# Debug_LEDs.net
KiCad netlist of a schematic drawn in Altium Designer
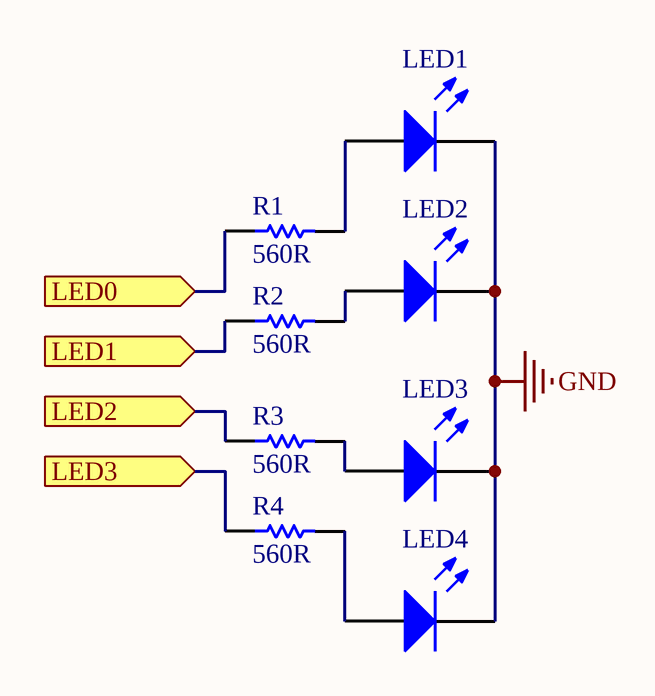
[diagram p0: Debug LEDs.SchDoc]

(export (version "E")
  (design (tool "Eeschema 10.0.6"))
  (components
    (comp (ref "LED1")
      (value "150080RS75000")
      (footprint "0805_A")
      (description "SMD mono-color Chip LED, WL-SMCW, Red")
      (fields (field (name "MANUFACTURER") "Wuerth Elektronik"))
      (libsource (lib "Altium Content Vault") (part "WE-LED_K1A2-2"))
    )
    (comp (ref "LED2")
      (value "150080GS75000")
      (footprint "0805_A")
      (description "SMD mono-color Chip LED, WL-SMCW, Green")
      (fields (field (name "MANUFACTURER") "Wuerth Elektronik"))
      (libsource (lib "Altium Content Vault") (part "WE-LED_K1A2-2"))
    )
    (comp (ref "LED3")
      (value "150080BS75000")
      (footprint "0805_A")
      (description "SMD mono-color Chip LED, WL-SMCW, Blue")
      (fields (field (name "MANUFACTURER") "Wuerth Elektronik"))
      (libsource (lib "Altium Content Vault") (part "WE-LED_K1A2-2"))
    )
    (comp (ref "LED4")
      (value "150080YS75000")
      (footprint "0805_A")
      (description "SMD mono-color Chip LED, WL-SMCW, Yellow")
      (fields (field (name "MANUFACTURER") "Wuerth Elektronik"))
      (libsource (lib "Altium Content Vault") (part "WE-LED_K1A2-2"))
    )
    (comp (ref "R1")
      (value "560R")
      (footprint "RESC0805(2012)_M")
      (description "560R 0.125W 1% 0805 (2012 Metric)  SMD")
      (fields (field (name "TOLERANCE") "1 %") (field (name "POWER") "0.125 W"))
      (libsource (lib "Altium Content Vault") (part "RES"))
    )
    (comp (ref "R2")
      (value "560R")
      (footprint "RESC0805(2012)_M")
      (description "560R 0.125W 1% 0805 (2012 Metric)  SMD")
      (fields (field (name "TOLERANCE") "1 %") (field (name "POWER") "0.125 W"))
      (libsource (lib "Altium Content Vault") (part "RES"))
    )
    (comp (ref "R3")
      (value "560R")
      (footprint "RESC0805(2012)_M")
      (description "560R 0.125W 1% 0805 (2012 Metric)  SMD")
      (fields (field (name "TOLERANCE") "1 %") (field (name "POWER") "0.125 W"))
      (libsource (lib "Altium Content Vault") (part "RES"))
    )
    (comp (ref "R4")
      (value "560R")
      (footprint "RESC0805(2012)_M")
      (description "560R 0.125W 1% 0805 (2012 Metric)  SMD")
      (fields (field (name "TOLERANCE") "1 %") (field (name "POWER") "0.125 W"))
      (libsource (lib "Altium Content Vault") (part "RES"))
    )
  )
  (nets
    (net (code "1") (name "/LED0") (class "Default")
      (node (ref "R1") (pin "1") (pinfunction "1_1") (pintype "passive"))
    )
    (net (code "2") (name "/LED1") (class "Default")
      (node (ref "R2") (pin "1") (pinfunction "1_1") (pintype "passive"))
    )
    (net (code "3") (name "/LED2") (class "Default")
      (node (ref "R3") (pin "1") (pinfunction "1_1") (pintype "passive"))
    )
    (net (code "4") (name "/LED3") (class "Default")
      (node (ref "R4") (pin "1") (pinfunction "1_1") (pintype "passive"))
    )
    (net (code "5") (name "GND") (class "Default")
      (node (ref "LED1") (pin "1") (pinfunction "K_1") (pintype "passive"))
      (node (ref "LED2") (pin "1") (pinfunction "K_1") (pintype "passive"))
      (node (ref "LED3") (pin "1") (pinfunction "K_1") (pintype "passive"))
      (node (ref "LED4") (pin "1") (pinfunction "K_1") (pintype "passive"))
    )
    (net (code "6") (name "Net-(LED1-A)") (class "Default")
      (node (ref "LED1") (pin "2") (pinfunction "A_2") (pintype "passive"))
      (node (ref "R1") (pin "2") (pinfunction "2_2") (pintype "passive"))
    )
    (net (code "7") (name "Net-(LED2-A)") (class "Default")
      (node (ref "LED2") (pin "2") (pinfunction "A_2") (pintype "passive"))
      (node (ref "R2") (pin "2") (pinfunction "2_2") (pintype "passive"))
    )
    (net (code "8") (name "Net-(LED3-A)") (class "Default")
      (node (ref "LED3") (pin "2") (pinfunction "A_2") (pintype "passive"))
      (node (ref "R3") (pin "2") (pinfunction "2_2") (pintype "passive"))
    )
    (net (code "9") (name "Net-(LED4-A)") (class "Default")
      (node (ref "LED4") (pin "2") (pinfunction "A_2") (pintype "passive"))
      (node (ref "R4") (pin "2") (pinfunction "2_2") (pintype "passive"))
    )
  )
)
